# WidefieldController.net
KiCad netlist of a schematic drawn in EAGLE
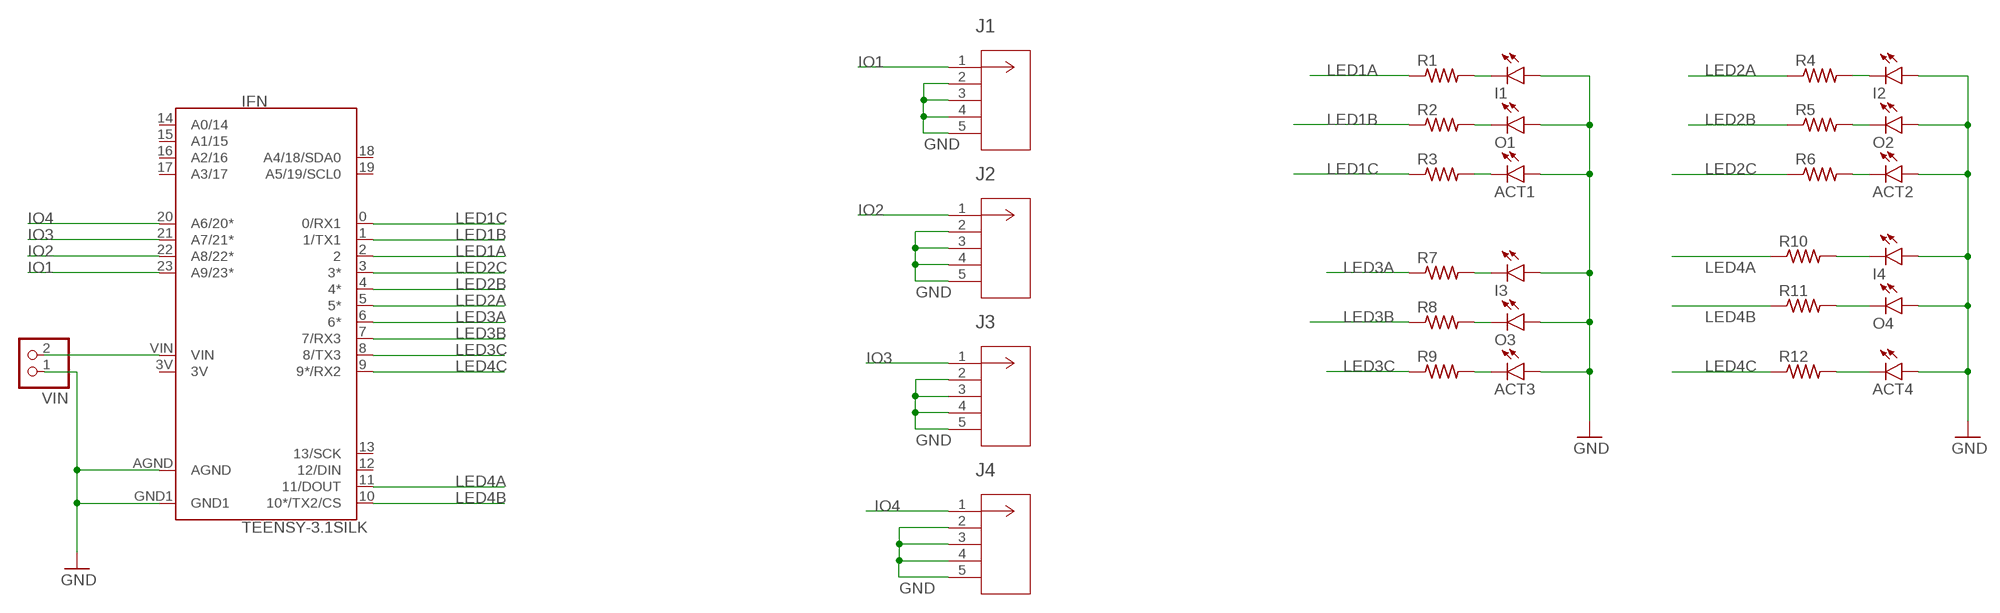
[diagram p0: schematic, sheet 1]

(export (version "E")
  (design (tool "Eeschema 10.0.6"))
  (components
    (comp (ref "ACT1")
      (value "LEDCHIPLED_0603")
      (footprint "eagle-import:CHIPLED_0603")
      (libsource (lib "eagle-import") (part "LEDCHIPLED_0603"))
    )
    (comp (ref "ACT2")
      (value "LEDCHIPLED_0603")
      (footprint "eagle-import:CHIPLED_0603")
      (libsource (lib "eagle-import") (part "LEDCHIPLED_0603"))
    )
    (comp (ref "ACT3")
      (value "LEDCHIPLED_0603")
      (footprint "eagle-import:CHIPLED_0603")
      (libsource (lib "eagle-import") (part "LEDCHIPLED_0603"))
    )
    (comp (ref "ACT4")
      (value "LEDCHIPLED_0603")
      (footprint "eagle-import:CHIPLED_0603")
      (libsource (lib "eagle-import") (part "LEDCHIPLED_0603"))
    )
    (comp (ref "I1")
      (value "LEDCHIPLED_0603")
      (footprint "eagle-import:CHIPLED_0603")
      (libsource (lib "eagle-import") (part "LEDCHIPLED_0603"))
    )
    (comp (ref "I2")
      (value "LEDCHIPLED_0603")
      (footprint "eagle-import:CHIPLED_0603")
      (libsource (lib "eagle-import") (part "LEDCHIPLED_0603"))
    )
    (comp (ref "I3")
      (value "LEDCHIPLED_0603")
      (footprint "eagle-import:CHIPLED_0603")
      (libsource (lib "eagle-import") (part "LEDCHIPLED_0603"))
    )
    (comp (ref "I4")
      (value "LEDCHIPLED_0603")
      (footprint "eagle-import:CHIPLED_0603")
      (libsource (lib "eagle-import") (part "LEDCHIPLED_0603"))
    )
    (comp (ref "IFN")
      (value "TEENSY-3.1SILK")
      (footprint "eagle-import:TEENSY-3.1")
      (libsource (lib "eagle-import") (part "TEENSY-3.1SILK"))
    )
    (comp (ref "J1")
      (value "5-1634503-1")
      (footprint "eagle-import:CONN5_5-1634503-1_TEC")
      (fields (field (name "COPYRIGHT") "Copyright (C) 2016 Accelerated Designs. All rights reserved"))
      (libsource (lib "eagle-import") (part "5-1634503-1"))
    )
    (comp (ref "J2")
      (value "5-1634503-1")
      (footprint "eagle-import:CONN5_5-1634503-1_TEC")
      (fields (field (name "COPYRIGHT") "Copyright (C) 2016 Accelerated Designs. All rights reserved"))
      (libsource (lib "eagle-import") (part "5-1634503-1"))
    )
    (comp (ref "J3")
      (value "5-1634503-1")
      (footprint "eagle-import:CONN5_5-1634503-1_TEC")
      (fields (field (name "COPYRIGHT") "Copyright (C) 2016 Accelerated Designs. All rights reserved"))
      (libsource (lib "eagle-import") (part "5-1634503-1"))
    )
    (comp (ref "J4")
      (value "5-1634503-1")
      (footprint "eagle-import:CONN5_5-1634503-1_TEC")
      (fields (field (name "COPYRIGHT") "Copyright (C) 2016 Accelerated Designs. All rights reserved"))
      (libsource (lib "eagle-import") (part "5-1634503-1"))
    )
    (comp (ref "O1")
      (value "LEDCHIPLED_0603")
      (footprint "eagle-import:CHIPLED_0603")
      (libsource (lib "eagle-import") (part "LEDCHIPLED_0603"))
    )
    (comp (ref "O2")
      (value "LEDCHIPLED_0603")
      (footprint "eagle-import:CHIPLED_0603")
      (libsource (lib "eagle-import") (part "LEDCHIPLED_0603"))
    )
    (comp (ref "O3")
      (value "LEDCHIPLED_0603")
      (footprint "eagle-import:CHIPLED_0603")
      (libsource (lib "eagle-import") (part "LEDCHIPLED_0603"))
    )
    (comp (ref "O4")
      (value "LEDCHIPLED_0603")
      (footprint "eagle-import:CHIPLED_0603")
      (libsource (lib "eagle-import") (part "LEDCHIPLED_0603"))
    )
    (comp (ref "R1")
      (value "R-US_R0603")
      (footprint "eagle-import:R0603")
      (libsource (lib "eagle-import") (part "R-US_R0603"))
    )
    (comp (ref "R2")
      (value "R-US_R0603")
      (footprint "eagle-import:R0603")
      (libsource (lib "eagle-import") (part "R-US_R0603"))
    )
    (comp (ref "R3")
      (value "R-US_R0603")
      (footprint "eagle-import:R0603")
      (libsource (lib "eagle-import") (part "R-US_R0603"))
    )
    (comp (ref "R4")
      (value "R-US_R0603")
      (footprint "eagle-import:R0603")
      (libsource (lib "eagle-import") (part "R-US_R0603"))
    )
    (comp (ref "R5")
      (value "R-US_R0603")
      (footprint "eagle-import:R0603")
      (libsource (lib "eagle-import") (part "R-US_R0603"))
    )
    (comp (ref "R6")
      (value "R-US_R0603")
      (footprint "eagle-import:R0603")
      (libsource (lib "eagle-import") (part "R-US_R0603"))
    )
    (comp (ref "R7")
      (value "R-US_R0603")
      (footprint "eagle-import:R0603")
      (libsource (lib "eagle-import") (part "R-US_R0603"))
    )
    (comp (ref "R8")
      (value "R-US_R0603")
      (footprint "eagle-import:R0603")
      (libsource (lib "eagle-import") (part "R-US_R0603"))
    )
    (comp (ref "R9")
      (value "R-US_R0603")
      (footprint "eagle-import:R0603")
      (libsource (lib "eagle-import") (part "R-US_R0603"))
    )
    (comp (ref "R10")
      (value "R-US_R0603")
      (footprint "eagle-import:R0603")
      (libsource (lib "eagle-import") (part "R-US_R0603"))
    )
    (comp (ref "R11")
      (value "R-US_R0603")
      (footprint "eagle-import:R0603")
      (libsource (lib "eagle-import") (part "R-US_R0603"))
    )
    (comp (ref "R12")
      (value "R-US_R0603")
      (footprint "eagle-import:R0603")
      (libsource (lib "eagle-import") (part "R-US_R0603"))
    )
    (comp (ref "VIN")
      (value "PINHD-1X2")
      (footprint "eagle-import:1X02")
      (libsource (lib "eagle-import") (part "PINHD-1X2"))
    )
  )
  (nets
    (net (code "1") (name "/3V") (class "Default")
      (node (ref "IFN") (pin "3V") (pinfunction "3V_3V") (pintype "power_in"))
    )
    (net (code "2") (name "/IO1") (class "Default")
      (node (ref "IFN") (pin "23") (pinfunction "A9/23*_23") (pintype "bidirectional"))
      (node (ref "J1") (pin "1") (pinfunction "1_1") (pintype "passive"))
    )
    (net (code "3") (name "/IO2") (class "Default")
      (node (ref "IFN") (pin "22") (pinfunction "A8/22*_22") (pintype "bidirectional"))
      (node (ref "J2") (pin "1") (pinfunction "1_1") (pintype "passive"))
    )
    (net (code "4") (name "/IO3") (class "Default")
      (node (ref "IFN") (pin "21") (pinfunction "A7/21*_21") (pintype "bidirectional"))
      (node (ref "J3") (pin "1") (pinfunction "1_1") (pintype "passive"))
    )
    (net (code "5") (name "/IO4") (class "Default")
      (node (ref "IFN") (pin "20") (pinfunction "A6/20*_20") (pintype "bidirectional"))
      (node (ref "J4") (pin "1") (pinfunction "1_1") (pintype "passive"))
    )
    (net (code "6") (name "/LED1A") (class "Default")
      (node (ref "IFN") (pin "2") (pinfunction "2_2") (pintype "bidirectional"))
      (node (ref "R1") (pin "1") (pinfunction "1_1") (pintype "passive"))
    )
    (net (code "7") (name "/LED1B") (class "Default")
      (node (ref "IFN") (pin "1") (pinfunction "1/TX1_1") (pintype "bidirectional"))
      (node (ref "R2") (pin "1") (pinfunction "1_1") (pintype "passive"))
    )
    (net (code "8") (name "/LED1C") (class "Default")
      (node (ref "IFN") (pin "0") (pinfunction "0/RX1_0") (pintype "bidirectional"))
      (node (ref "R3") (pin "1") (pinfunction "1_1") (pintype "passive"))
    )
    (net (code "9") (name "/LED2A") (class "Default")
      (node (ref "IFN") (pin "5") (pinfunction "5*_5") (pintype "bidirectional"))
      (node (ref "R4") (pin "1") (pinfunction "1_1") (pintype "passive"))
    )
    (net (code "10") (name "/LED2B") (class "Default")
      (node (ref "IFN") (pin "4") (pinfunction "4*_4") (pintype "bidirectional"))
      (node (ref "R5") (pin "1") (pinfunction "1_1") (pintype "passive"))
    )
    (net (code "11") (name "/LED2C") (class "Default")
      (node (ref "IFN") (pin "3") (pinfunction "3*_3") (pintype "bidirectional"))
      (node (ref "R6") (pin "1") (pinfunction "1_1") (pintype "passive"))
    )
    (net (code "12") (name "/LED3A") (class "Default")
      (node (ref "IFN") (pin "6") (pinfunction "6*_6") (pintype "bidirectional"))
      (node (ref "R7") (pin "1") (pinfunction "1_1") (pintype "passive"))
    )
    (net (code "13") (name "/LED3B") (class "Default")
      (node (ref "IFN") (pin "7") (pinfunction "7/RX3_7") (pintype "bidirectional"))
      (node (ref "R8") (pin "1") (pinfunction "1_1") (pintype "passive"))
    )
    (net (code "14") (name "/LED3C") (class "Default")
      (node (ref "IFN") (pin "8") (pinfunction "8/TX3_8") (pintype "bidirectional"))
      (node (ref "R9") (pin "1") (pinfunction "1_1") (pintype "passive"))
    )
    (net (code "15") (name "/LED4A") (class "Default")
      (node (ref "IFN") (pin "11") (pinfunction "11/DOUT_11") (pintype "bidirectional"))
      (node (ref "R10") (pin "1") (pinfunction "1_1") (pintype "passive"))
    )
    (net (code "16") (name "/LED4B") (class "Default")
      (node (ref "IFN") (pin "10") (pinfunction "10*/TX2/CS_10") (pintype "bidirectional"))
      (node (ref "R11") (pin "1") (pinfunction "1_1") (pintype "passive"))
    )
    (net (code "17") (name "/LED4C") (class "Default")
      (node (ref "IFN") (pin "9") (pinfunction "9*/RX2_9") (pintype "bidirectional"))
      (node (ref "R12") (pin "1") (pinfunction "1_1") (pintype "passive"))
    )
    (net (code "18") (name "GND") (class "Default")
      (node (ref "ACT1") (pin "A") (pinfunction "A_A") (pintype "passive"))
      (node (ref "ACT2") (pin "A") (pinfunction "A_A") (pintype "passive"))
      (node (ref "ACT3") (pin "A") (pinfunction "A_A") (pintype "passive"))
      (node (ref "ACT4") (pin "A") (pinfunction "A_A") (pintype "passive"))
      (node (ref "I1") (pin "A") (pinfunction "A_A") (pintype "passive"))
      (node (ref "I2") (pin "A") (pinfunction "A_A") (pintype "passive"))
      (node (ref "I3") (pin "A") (pinfunction "A_A") (pintype "passive"))
      (node (ref "I4") (pin "A") (pinfunction "A_A") (pintype "passive"))
      (node (ref "IFN") (pin "AGND") (pinfunction "AGND_AGND") (pintype "power_in"))
      (node (ref "IFN") (pin "GND1") (pinfunction "GND1_GND1") (pintype "power_in"))
      (node (ref "J1") (pin "2") (pinfunction "2_2") (pintype "passive"))
      (node (ref "J1") (pin "3") (pinfunction "3_3") (pintype "passive"))
      (node (ref "J1") (pin "4") (pinfunction "4_4") (pintype "passive"))
      (node (ref "J1") (pin "5") (pinfunction "5_5") (pintype "passive"))
      (node (ref "J2") (pin "2") (pinfunction "2_2") (pintype "passive"))
      (node (ref "J2") (pin "3") (pinfunction "3_3") (pintype "passive"))
      (node (ref "J2") (pin "4") (pinfunction "4_4") (pintype "passive"))
      (node (ref "J2") (pin "5") (pinfunction "5_5") (pintype "passive"))
      (node (ref "J3") (pin "2") (pinfunction "2_2") (pintype "passive"))
      (node (ref "J3") (pin "3") (pinfunction "3_3") (pintype "passive"))
      (node (ref "J3") (pin "4") (pinfunction "4_4") (pintype "passive"))
      (node (ref "J3") (pin "5") (pinfunction "5_5") (pintype "passive"))
      (node (ref "J4") (pin "2") (pinfunction "2_2") (pintype "passive"))
      (node (ref "J4") (pin "3") (pinfunction "3_3") (pintype "passive"))
      (node (ref "J4") (pin "4") (pinfunction "4_4") (pintype "passive"))
      (node (ref "J4") (pin "5") (pinfunction "5_5") (pintype "passive"))
      (node (ref "O1") (pin "A") (pinfunction "A_A") (pintype "passive"))
      (node (ref "O2") (pin "A") (pinfunction "A_A") (pintype "passive"))
      (node (ref "O3") (pin "A") (pinfunction "A_A") (pintype "passive"))
      (node (ref "O4") (pin "A") (pinfunction "A_A") (pintype "passive"))
      (node (ref "VIN") (pin "1") (pinfunction "1_1") (pintype "passive"))
    )
    (net (code "19") (name "Net-(ACT1-PadC)") (class "Default")
      (node (ref "ACT1") (pin "C") (pinfunction "C_C") (pintype "passive"))
      (node (ref "R3") (pin "2") (pinfunction "2_2") (pintype "passive"))
    )
    (net (code "20") (name "Net-(ACT2-PadC)") (class "Default")
      (node (ref "ACT2") (pin "C") (pinfunction "C_C") (pintype "passive"))
      (node (ref "R6") (pin "2") (pinfunction "2_2") (pintype "passive"))
    )
    (net (code "21") (name "Net-(ACT3-PadC)") (class "Default")
      (node (ref "ACT3") (pin "C") (pinfunction "C_C") (pintype "passive"))
      (node (ref "R9") (pin "2") (pinfunction "2_2") (pintype "passive"))
    )
    (net (code "22") (name "Net-(ACT4-PadC)") (class "Default")
      (node (ref "ACT4") (pin "C") (pinfunction "C_C") (pintype "passive"))
      (node (ref "R12") (pin "2") (pinfunction "2_2") (pintype "passive"))
    )
    (net (code "23") (name "Net-(I1-PadC)") (class "Default")
      (node (ref "I1") (pin "C") (pinfunction "C_C") (pintype "passive"))
      (node (ref "R1") (pin "2") (pinfunction "2_2") (pintype "passive"))
    )
    (net (code "24") (name "Net-(I2-PadC)") (class "Default")
      (node (ref "I2") (pin "C") (pinfunction "C_C") (pintype "passive"))
      (node (ref "R4") (pin "2") (pinfunction "2_2") (pintype "passive"))
    )
    (net (code "25") (name "Net-(I3-PadC)") (class "Default")
      (node (ref "I3") (pin "C") (pinfunction "C_C") (pintype "passive"))
      (node (ref "R7") (pin "2") (pinfunction "2_2") (pintype "passive"))
    )
    (net (code "26") (name "Net-(I4-PadC)") (class "Default")
      (node (ref "I4") (pin "C") (pinfunction "C_C") (pintype "passive"))
      (node (ref "R10") (pin "2") (pinfunction "2_2") (pintype "passive"))
    )
    (net (code "27") (name "Net-(IFN-PadVIN)") (class "Default")
      (node (ref "IFN") (pin "VIN") (pinfunction "VIN_VIN") (pintype "power_in"))
      (node (ref "VIN") (pin "2") (pinfunction "2_2") (pintype "passive"))
    )
    (net (code "28") (name "Net-(O1-PadC)") (class "Default")
      (node (ref "O1") (pin "C") (pinfunction "C_C") (pintype "passive"))
      (node (ref "R2") (pin "2") (pinfunction "2_2") (pintype "passive"))
    )
    (net (code "29") (name "Net-(O2-PadC)") (class "Default")
      (node (ref "O2") (pin "C") (pinfunction "C_C") (pintype "passive"))
      (node (ref "R5") (pin "2") (pinfunction "2_2") (pintype "passive"))
    )
    (net (code "30") (name "Net-(O3-PadC)") (class "Default")
      (node (ref "O3") (pin "C") (pinfunction "C_C") (pintype "passive"))
      (node (ref "R8") (pin "2") (pinfunction "2_2") (pintype "passive"))
    )
    (net (code "31") (name "Net-(O4-PadC)") (class "Default")
      (node (ref "O4") (pin "C") (pinfunction "C_C") (pintype "passive"))
      (node (ref "R11") (pin "2") (pinfunction "2_2") (pintype "passive"))
    )
    (net (code "32") (name "unconnected-(IFN-12{slash}DIN-Pad12)") (class "Default")
      (node (ref "IFN") (pin "12") (pinfunction "12/DIN_12") (pintype "bidirectional"))
    )
    (net (code "33") (name "unconnected-(IFN-13{slash}SCK-Pad13)") (class "Default")
      (node (ref "IFN") (pin "13") (pinfunction "13/SCK_13") (pintype "bidirectional"))
    )
    (net (code "34") (name "unconnected-(IFN-A0{slash}14-Pad14)") (class "Default")
      (node (ref "IFN") (pin "14") (pinfunction "A0/14_14") (pintype "bidirectional"))
    )
    (net (code "35") (name "unconnected-(IFN-A1{slash}15-Pad15)") (class "Default")
      (node (ref "IFN") (pin "15") (pinfunction "A1/15_15") (pintype "bidirectional"))
    )
    (net (code "36") (name "unconnected-(IFN-A2{slash}16-Pad16)") (class "Default")
      (node (ref "IFN") (pin "16") (pinfunction "A2/16_16") (pintype "bidirectional"))
    )
    (net (code "37") (name "unconnected-(IFN-A3{slash}17-Pad17)") (class "Default")
      (node (ref "IFN") (pin "17") (pinfunction "A3/17_17") (pintype "bidirectional"))
    )
    (net (code "38") (name "unconnected-(IFN-A4{slash}18{slash}SDA0-Pad18)") (class "Default")
      (node (ref "IFN") (pin "18") (pinfunction "A4/18/SDA0_18") (pintype "bidirectional"))
    )
    (net (code "39") (name "unconnected-(IFN-A5{slash}19{slash}SCL0-Pad19)") (class "Default")
      (node (ref "IFN") (pin "19") (pinfunction "A5/19/SCL0_19") (pintype "bidirectional"))
    )
  )
)
